# Reset.net
KiCad netlist of a schematic drawn in Altium Designer
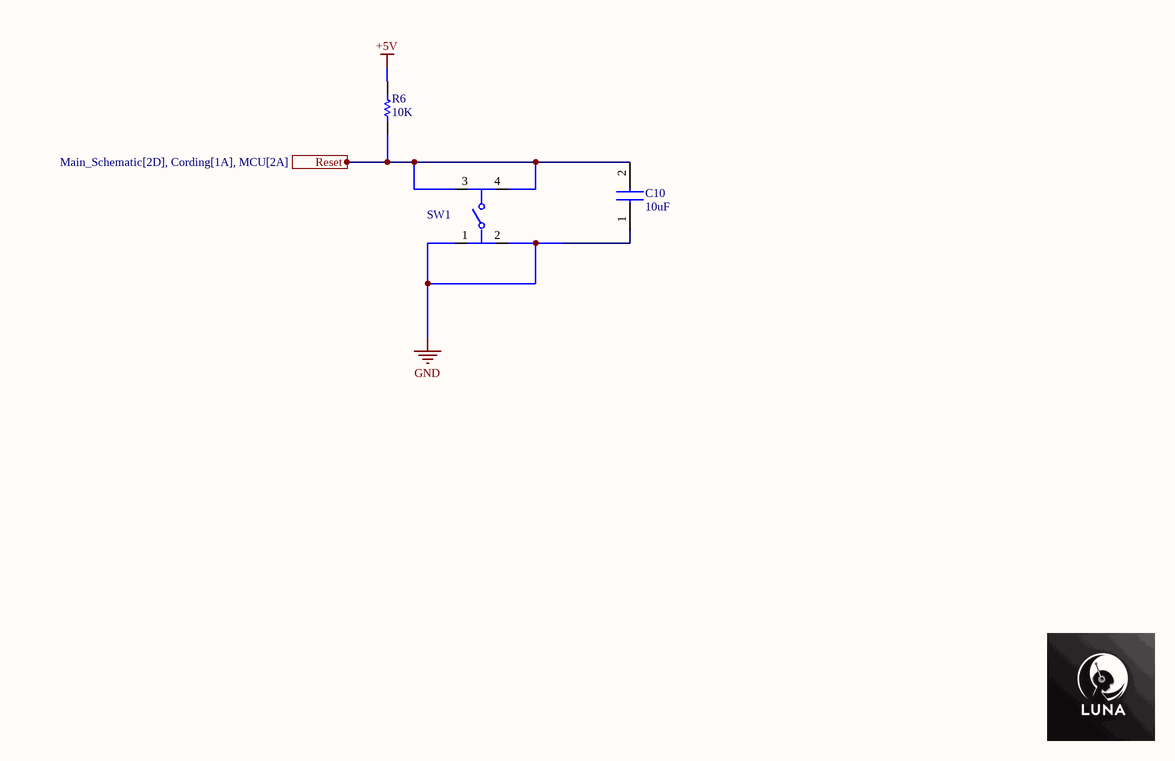
[diagram p0: Reset.SchDoc]

(export (version "E")
  (design (tool "Eeschema 10.0.6"))
  (components
    (comp (ref "C10")
      (value "10uF")
      (footprint "SamacSys:CAPC1608X90N")
      (description "CL10A106KP8NNNC Capacitor")
      (fields
        (field (name "MANUFACTURER_PART_NUMBER") "CL10A106KP8NNNC")
        (field (name "MOUSER PART NUMBER") "187-CL10A106KP8NNNC")
      )
      (libsource (lib "*") (part "CL10A106KP8NNNC"))
    )
    (comp (ref "R6")
      (value "10K")
      (footprint "RESC1608X55X25ML10T15")
      (fields (field (name "MANUFACTURER") "Yageo") (field (name "TOLERANCE") "5%"))
      (libsource (lib "Altium Content Vault") (part "RES-2"))
    )
    (comp (ref "SW1")
      (value "PTS526SK15SMTR2LFS")
      (footprint "FP-PTS526SK15SMTR2LFS-MFG")
      (description "TACT 5.2 X 5.2, 1.5 MM H, 260GF,")
      (fields
        (field (name "MANUFACTURER") "C&K")
        (field (name "OCTOPART") "https://octopart.com/pts526+sk15+smtr2+lfs-c%26k+components-100617999")
      )
      (libsource (lib "Altium Content Vault") (part "b8895f3f4cefb76e1819d2863dba89b"))
    )
  )
  (nets
    (net (code "1") (name "+5V") (class "Default")
      (node (ref "R6") (pin "2") (pinfunction "2_2") (pintype "passive"))
    )
    (net (code "2") (name "/Reset") (class "Default")
      (node (ref "C10") (pin "2") (pinfunction "2_2") (pintype "passive"))
      (node (ref "R6") (pin "1") (pinfunction "1_1") (pintype "passive"))
      (node (ref "SW1") (pin "3") (pinfunction "3_3") (pintype "passive"))
      (node (ref "SW1") (pin "4") (pinfunction "4_4") (pintype "passive"))
    )
    (net (code "3") (name "GND") (class "Default")
      (node (ref "C10") (pin "1") (pinfunction "1_1") (pintype "passive"))
      (node (ref "SW1") (pin "1") (pinfunction "1_1") (pintype "passive"))
      (node (ref "SW1") (pin "2") (pinfunction "2_2") (pintype "passive"))
    )
  )
)
